# esquem_tico.net
KiCad netlist of a schematic drawn in EAGLE
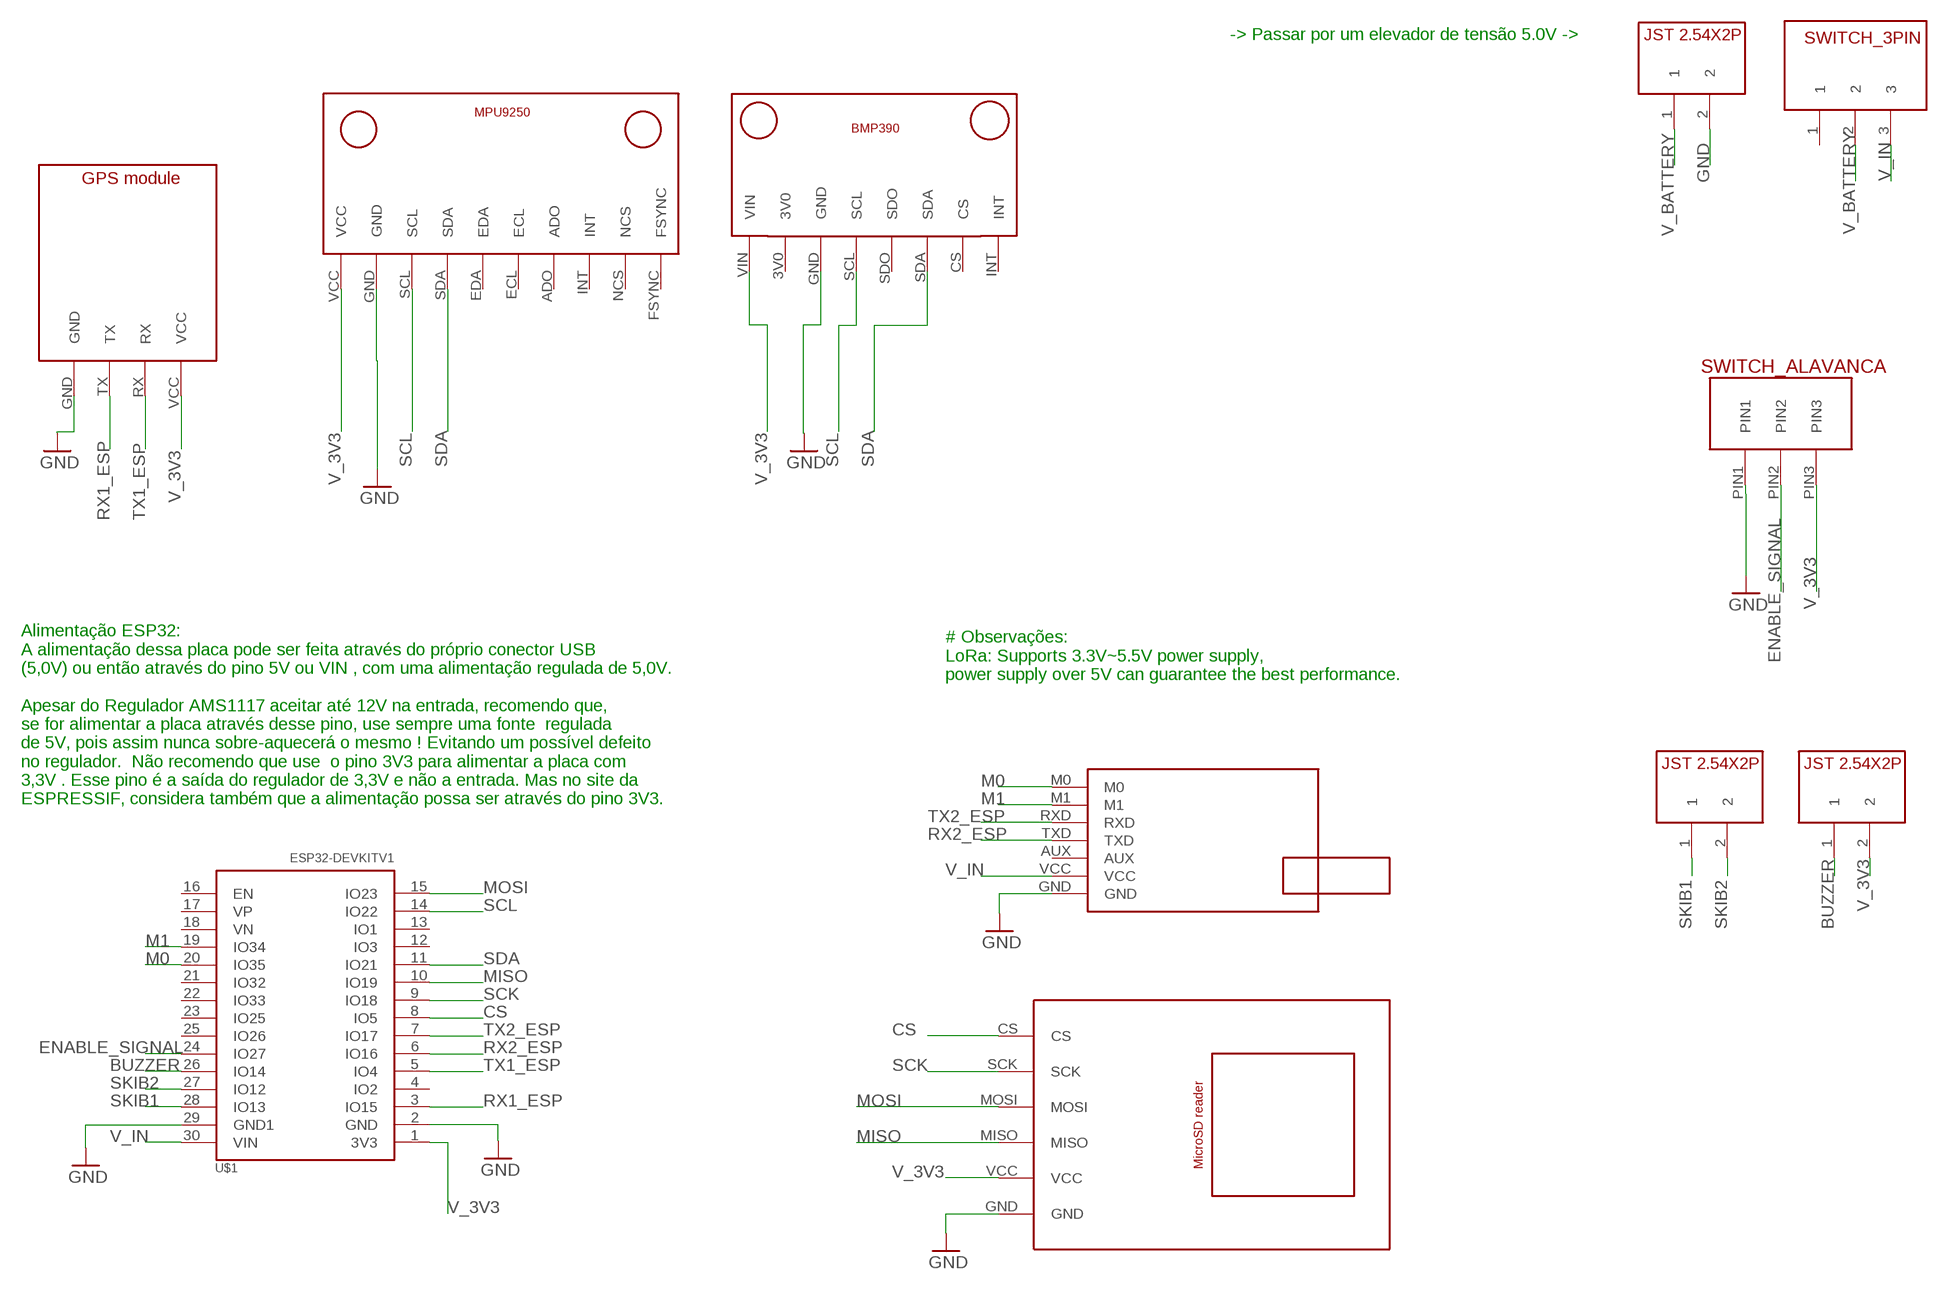
[diagram p0: schematic, sheet 1]

(export (version "E")
  (design (tool "Eeschema 10.0.6"))
  (components
    (comp (ref "U$1")
      (value "ESP32DEVKITV1")
      (footprint "eagle-import:ESP32-DEVKITV1")
      (libsource (lib "eagle-import") (part "ESP32DEVKITV1"))
    )
    (comp (ref "U$2")
      (value "E22-400T30D")
      (footprint "eagle-import:E22-400T30D_FOOTPRINT")
      (libsource (lib "eagle-import") (part "E22-400T30D"))
    )
    (comp (ref "U$3")
      (value "GPS_MODULE")
      (footprint "eagle-import:GPS_MODULE_FOOTPRINT")
      (libsource (lib "eagle-import") (part "GPS_MODULE"))
    )
    (comp (ref "U$5")
      (value "SWITCH_ALAVANCA")
      (footprint "eagle-import:SWITCH_ALAVANCA_FOOTPRINT")
      (libsource (lib "eagle-import") (part "SWITCH_ALAVANCA"))
    )
    (comp (ref "U$7")
      (value "MICROSD_READER")
      (footprint "eagle-import:MICROSD_READER_FOOTPRINT")
      (libsource (lib "eagle-import") (part "MICROSD_READER"))
    )
    (comp (ref "U$8")
      (value "JST2.54X2P")
      (footprint "eagle-import:JST2.54X2P_FOOTPRINT")
      (libsource (lib "eagle-import") (part "JST2.54X2P"))
    )
    (comp (ref "U$9")
      (value "JST2.54X2P")
      (footprint "eagle-import:JST2.54X2P_FOOTPRINT")
      (libsource (lib "eagle-import") (part "JST2.54X2P"))
    )
    (comp (ref "U$10")
      (value "MPU9250V1")
      (footprint "eagle-import:MPU9250_FOOTPRINT")
      (libsource (lib "eagle-import") (part "MPU9250V1"))
    )
    (comp (ref "U$11")
      (value "SWITCH_3PIN")
      (footprint "eagle-import:SWITCH_3PIN")
      (libsource (lib "eagle-import") (part "SWITCH_3PIN"))
    )
    (comp (ref "U$12")
      (value "JST2.54X2P")
      (footprint "eagle-import:JST2.54X2P_FOOTPRINT")
      (libsource (lib "eagle-import") (part "JST2.54X2P"))
    )
    (comp (ref "U$13")
      (value "BMP390V1")
      (footprint "eagle-import:BMP390_FOOTPRINT")
      (libsource (lib "eagle-import") (part "BMP390V1"))
    )
  )
  (nets
    (net (code "1") (name "/BUZZER") (class "Default")
      (node (ref "U$1") (pin "26") (pinfunction "IO14_26") (pintype "bidirectional"))
      (node (ref "U$9") (pin "1") (pinfunction "1_1") (pintype "bidirectional"))
    )
    (net (code "2") (name "/CS") (class "Default")
      (node (ref "U$1") (pin "8") (pinfunction "IO5_8") (pintype "bidirectional"))
      (node (ref "U$7") (pin "CS") (pinfunction "CS_CS") (pintype "bidirectional"))
    )
    (net (code "3") (name "/ENABLE_SIGNAL") (class "Default")
      (node (ref "U$1") (pin "24") (pinfunction "IO27_24") (pintype "bidirectional"))
      (node (ref "U$5") (pin "PIN2") (pinfunction "PIN2_PIN2") (pintype "bidirectional"))
    )
    (net (code "4") (name "/M0") (class "Default")
      (node (ref "U$1") (pin "20") (pinfunction "IO35_20") (pintype "bidirectional"))
      (node (ref "U$2") (pin "M0") (pinfunction "M0_M0") (pintype "bidirectional"))
    )
    (net (code "5") (name "/M1") (class "Default")
      (node (ref "U$1") (pin "19") (pinfunction "IO34_19") (pintype "bidirectional"))
      (node (ref "U$2") (pin "M1") (pinfunction "M1_M1") (pintype "bidirectional"))
    )
    (net (code "6") (name "/MISO") (class "Default")
      (node (ref "U$1") (pin "10") (pinfunction "IO19_10") (pintype "bidirectional"))
      (node (ref "U$7") (pin "MISO") (pinfunction "MISO_MISO") (pintype "bidirectional"))
    )
    (net (code "7") (name "/MOSI") (class "Default")
      (node (ref "U$1") (pin "15") (pinfunction "IO23_15") (pintype "bidirectional"))
      (node (ref "U$7") (pin "MOSI") (pinfunction "MOSI_MOSI") (pintype "bidirectional"))
    )
    (net (code "8") (name "/RX1_ESP") (class "Default")
      (node (ref "U$1") (pin "3") (pinfunction "IO15_3") (pintype "bidirectional"))
      (node (ref "U$3") (pin "TX") (pinfunction "TX_TX") (pintype "bidirectional"))
    )
    (net (code "9") (name "/RX2_ESP") (class "Default")
      (node (ref "U$1") (pin "6") (pinfunction "IO16_6") (pintype "bidirectional"))
      (node (ref "U$2") (pin "TXD") (pinfunction "TXD_TXD") (pintype "bidirectional"))
    )
    (net (code "10") (name "/SCK") (class "Default")
      (node (ref "U$1") (pin "9") (pinfunction "IO18_9") (pintype "bidirectional"))
      (node (ref "U$7") (pin "SCK") (pinfunction "SCK_SCK") (pintype "bidirectional"))
    )
    (net (code "11") (name "/SCL") (class "Default")
      (node (ref "U$1") (pin "14") (pinfunction "IO22_14") (pintype "bidirectional"))
      (node (ref "U$10") (pin "SCL") (pinfunction "SCL_SCL") (pintype "bidirectional"))
      (node (ref "U$13") (pin "SCL") (pinfunction "SCL_SCL") (pintype "bidirectional"))
    )
    (net (code "12") (name "/SDA") (class "Default")
      (node (ref "U$1") (pin "11") (pinfunction "IO21_11") (pintype "bidirectional"))
      (node (ref "U$10") (pin "SDA") (pinfunction "SDA_SDA") (pintype "bidirectional"))
      (node (ref "U$13") (pin "SDA") (pinfunction "SDA_SDA") (pintype "bidirectional"))
    )
    (net (code "13") (name "/SKIB1") (class "Default")
      (node (ref "U$1") (pin "28") (pinfunction "IO13_28") (pintype "bidirectional"))
      (node (ref "U$8") (pin "1") (pinfunction "1_1") (pintype "bidirectional"))
    )
    (net (code "14") (name "/SKIB2") (class "Default")
      (node (ref "U$1") (pin "27") (pinfunction "IO12_27") (pintype "bidirectional"))
      (node (ref "U$8") (pin "2") (pinfunction "2_2") (pintype "bidirectional"))
    )
    (net (code "15") (name "/TX1_ESP") (class "Default")
      (node (ref "U$1") (pin "5") (pinfunction "IO4_5") (pintype "bidirectional"))
      (node (ref "U$3") (pin "RX") (pinfunction "RX_RX") (pintype "bidirectional"))
    )
    (net (code "16") (name "/TX2_ESP") (class "Default")
      (node (ref "U$1") (pin "7") (pinfunction "IO17_7") (pintype "bidirectional"))
      (node (ref "U$2") (pin "RXD") (pinfunction "RXD_RXD") (pintype "bidirectional"))
    )
    (net (code "17") (name "/V_3V3") (class "Default")
      (node (ref "U$1") (pin "1") (pinfunction "3V3_1") (pintype "bidirectional"))
      (node (ref "U$10") (pin "VCC") (pinfunction "VCC_VCC") (pintype "bidirectional"))
      (node (ref "U$13") (pin "VIN") (pinfunction "VIN_VIN") (pintype "bidirectional"))
      (node (ref "U$3") (pin "VCC") (pinfunction "VCC_VCC") (pintype "bidirectional"))
      (node (ref "U$5") (pin "PIN3") (pinfunction "PIN3_PIN3") (pintype "bidirectional"))
      (node (ref "U$7") (pin "VCC") (pinfunction "VCC_VCC") (pintype "bidirectional"))
      (node (ref "U$9") (pin "2") (pinfunction "2_2") (pintype "bidirectional"))
    )
    (net (code "18") (name "/V_BATTERY") (class "Default")
      (node (ref "U$11") (pin "2") (pinfunction "2_2") (pintype "bidirectional"))
      (node (ref "U$12") (pin "1") (pinfunction "1_1") (pintype "bidirectional"))
    )
    (net (code "19") (name "/V_IN") (class "Default")
      (node (ref "U$1") (pin "30") (pinfunction "VIN_30") (pintype "bidirectional"))
      (node (ref "U$11") (pin "3") (pinfunction "3_3") (pintype "bidirectional"))
      (node (ref "U$2") (pin "VCC") (pinfunction "VCC_VCC") (pintype "bidirectional"))
    )
    (net (code "20") (name "GND") (class "Default")
      (node (ref "U$1") (pin "2") (pinfunction "GND_2") (pintype "bidirectional"))
      (node (ref "U$1") (pin "29") (pinfunction "GND1_29") (pintype "bidirectional"))
      (node (ref "U$10") (pin "GND") (pinfunction "GND_GND") (pintype "bidirectional"))
      (node (ref "U$12") (pin "2") (pinfunction "2_2") (pintype "bidirectional"))
      (node (ref "U$13") (pin "GND") (pinfunction "GND_GND") (pintype "bidirectional"))
      (node (ref "U$2") (pin "GND") (pinfunction "GND_GND") (pintype "bidirectional"))
      (node (ref "U$3") (pin "GND") (pinfunction "GND_GND") (pintype "bidirectional"))
      (node (ref "U$5") (pin "PIN1") (pinfunction "PIN1_PIN1") (pintype "bidirectional"))
      (node (ref "U$7") (pin "GND") (pinfunction "GND_GND") (pintype "bidirectional"))
    )
    (net (code "21") (name "unconnected-(U$1-EN-Pad16)") (class "Default")
      (node (ref "U$1") (pin "16") (pinfunction "EN_16") (pintype "bidirectional"))
    )
    (net (code "22") (name "unconnected-(U$1-IO1-Pad13)") (class "Default")
      (node (ref "U$1") (pin "13") (pinfunction "IO1_13") (pintype "bidirectional"))
    )
    (net (code "23") (name "unconnected-(U$1-IO2-Pad4)") (class "Default")
      (node (ref "U$1") (pin "4") (pinfunction "IO2_4") (pintype "bidirectional"))
    )
    (net (code "24") (name "unconnected-(U$1-IO3-Pad12)") (class "Default")
      (node (ref "U$1") (pin "12") (pinfunction "IO3_12") (pintype "bidirectional"))
    )
    (net (code "25") (name "unconnected-(U$1-IO25-Pad23)") (class "Default")
      (node (ref "U$1") (pin "23") (pinfunction "IO25_23") (pintype "bidirectional"))
    )
    (net (code "26") (name "unconnected-(U$1-IO26-Pad25)") (class "Default")
      (node (ref "U$1") (pin "25") (pinfunction "IO26_25") (pintype "bidirectional"))
    )
    (net (code "27") (name "unconnected-(U$1-IO32-Pad21)") (class "Default")
      (node (ref "U$1") (pin "21") (pinfunction "IO32_21") (pintype "bidirectional"))
    )
    (net (code "28") (name "unconnected-(U$1-IO33-Pad22)") (class "Default")
      (node (ref "U$1") (pin "22") (pinfunction "IO33_22") (pintype "bidirectional"))
    )
    (net (code "29") (name "unconnected-(U$1-VN-Pad18)") (class "Default")
      (node (ref "U$1") (pin "18") (pinfunction "VN_18") (pintype "bidirectional"))
    )
    (net (code "30") (name "unconnected-(U$1-VP-Pad17)") (class "Default")
      (node (ref "U$1") (pin "17") (pinfunction "VP_17") (pintype "bidirectional"))
    )
    (net (code "31") (name "unconnected-(U$2-PadAUX)") (class "Default")
      (node (ref "U$2") (pin "AUX") (pinfunction "AUX_AUX") (pintype "bidirectional"))
    )
    (net (code "32") (name "unconnected-(U$10-PadADO)") (class "Default")
      (node (ref "U$10") (pin "ADO") (pinfunction "ADO_ADO") (pintype "bidirectional"))
    )
    (net (code "33") (name "unconnected-(U$10-PadECL)") (class "Default")
      (node (ref "U$10") (pin "ECL") (pinfunction "ECL_ECL") (pintype "bidirectional"))
    )
    (net (code "34") (name "unconnected-(U$10-PadEDA)") (class "Default")
      (node (ref "U$10") (pin "EDA") (pinfunction "EDA_EDA") (pintype "bidirectional"))
    )
    (net (code "35") (name "unconnected-(U$10-PadFSYNC)") (class "Default")
      (node (ref "U$10") (pin "FSYNC") (pinfunction "FSYNC_FSYNC") (pintype "bidirectional"))
    )
    (net (code "36") (name "unconnected-(U$10-PadINT)") (class "Default")
      (node (ref "U$10") (pin "INT") (pinfunction "INT_INT") (pintype "bidirectional"))
    )
    (net (code "37") (name "unconnected-(U$10-PadNCS)") (class "Default")
      (node (ref "U$10") (pin "NCS") (pinfunction "NCS_NCS") (pintype "bidirectional"))
    )
    (net (code "38") (name "unconnected-(U$11-Pad1)") (class "Default")
      (node (ref "U$11") (pin "1") (pinfunction "1_1") (pintype "bidirectional"))
    )
    (net (code "39") (name "unconnected-(U$13-Pad3V0)") (class "Default")
      (node (ref "U$13") (pin "3V0") (pinfunction "3V0_3V0") (pintype "bidirectional"))
    )
    (net (code "40") (name "unconnected-(U$13-PadCS)") (class "Default")
      (node (ref "U$13") (pin "CS") (pinfunction "CS_CS") (pintype "bidirectional"))
    )
    (net (code "41") (name "unconnected-(U$13-PadINT)") (class "Default")
      (node (ref "U$13") (pin "INT") (pinfunction "INT_INT") (pintype "bidirectional"))
    )
    (net (code "42") (name "unconnected-(U$13-PadSDO)") (class "Default")
      (node (ref "U$13") (pin "SDO") (pinfunction "SDO_SDO") (pintype "bidirectional"))
    )
  )
)
